# CtDSP_IO.net
KiCad netlist of a schematic drawn in Altium Designer
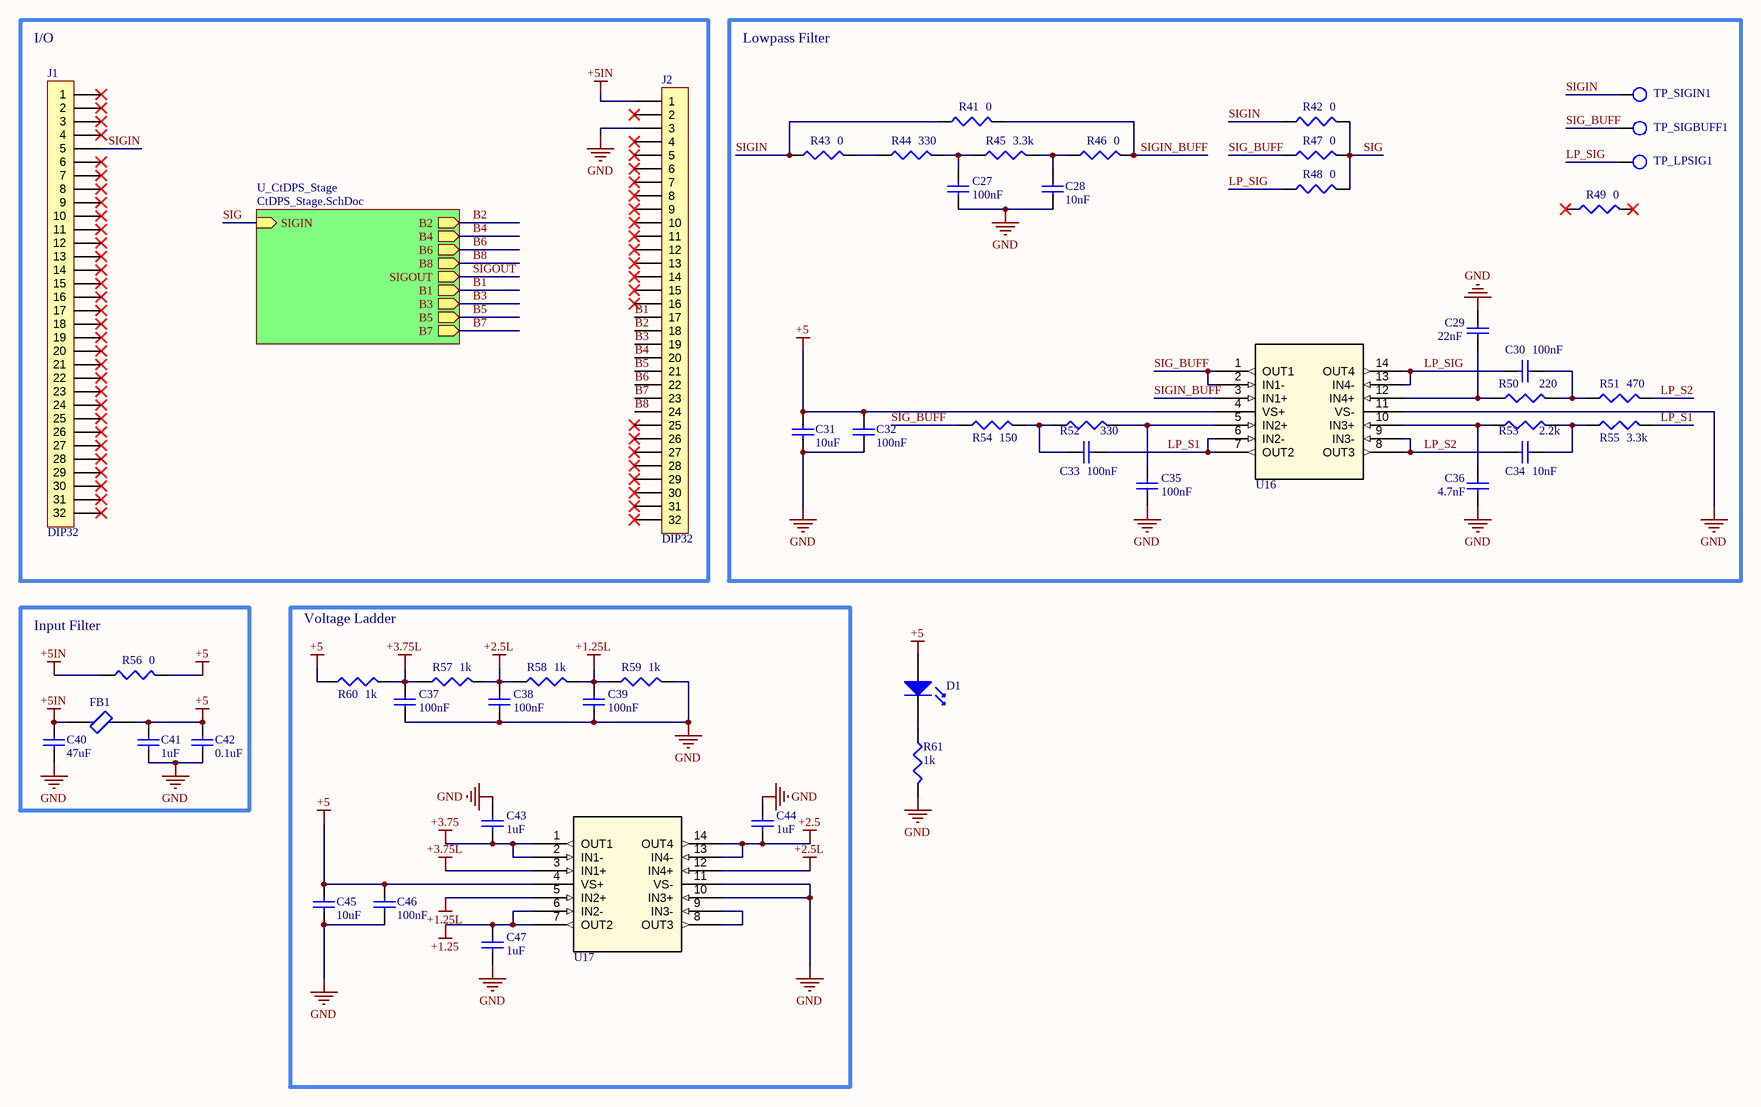
[diagram p0: CtDSP_IO.SchDoc]

(export (version "E")
  (design (tool "Eeschema 10.0.6"))
  (components
    (comp (ref "C27")
      (value "100nF")
      (footprint "C_0402")
      (fields (field (name "LCSC PART #") "C1525"))
      (libsource (lib "ctdsp") (part "C_0402"))
    )
    (comp (ref "C28")
      (value "10nF")
      (footprint "C_0402")
      (fields (field (name "LCSC PART #") "C15195"))
      (libsource (lib "ctdsp") (part "C_0402"))
    )
    (comp (ref "C29")
      (value "22nF")
      (footprint "C_0402")
      (fields (field (name "LCSC PART #") "C1532"))
      (libsource (lib "ctdsp") (part "C_0402"))
    )
    (comp (ref "C30")
      (value "100nF")
      (footprint "C_0402")
      (fields (field (name "LCSC PART #") "C1525"))
      (libsource (lib "ctdsp") (part "C_0402"))
    )
    (comp (ref "C31")
      (value "10uF")
      (footprint "C_0402")
      (fields (field (name "LCSC PART #") "C15525"))
      (libsource (lib "ctdsp") (part "C_0402"))
    )
    (comp (ref "C32")
      (value "100nF")
      (footprint "C_0402")
      (fields (field (name "LCSC PART #") "C1525"))
      (libsource (lib "ctdsp") (part "C_0402"))
    )
    (comp (ref "C33")
      (value "100nF")
      (footprint "C_0402")
      (fields (field (name "LCSC PART #") "C1525"))
      (libsource (lib "ctdsp") (part "C_0402"))
    )
    (comp (ref "C34")
      (value "10nF")
      (footprint "C_0402")
      (fields (field (name "LCSC PART #") "C15195"))
      (libsource (lib "ctdsp") (part "C_0402"))
    )
    (comp (ref "C35")
      (value "100nF")
      (footprint "C_0402")
      (fields (field (name "LCSC PART #") "C1525"))
      (libsource (lib "ctdsp") (part "C_0402"))
    )
    (comp (ref "C36")
      (value "4.7nF")
      (footprint "C_0402")
      (fields (field (name "LCSC PART #") "C1538"))
      (libsource (lib "ctdsp") (part "C_0402"))
    )
    (comp (ref "C37")
      (value "100nF")
      (footprint "C_0402")
      (fields (field (name "LCSC PART #") "C1525"))
      (libsource (lib "ctdsp") (part "C_0402"))
    )
    (comp (ref "C38")
      (value "100nF")
      (footprint "C_0402")
      (fields (field (name "LCSC PART #") "C1525"))
      (libsource (lib "ctdsp") (part "C_0402"))
    )
    (comp (ref "C39")
      (value "100nF")
      (footprint "C_0402")
      (fields (field (name "LCSC PART #") "C1525"))
      (libsource (lib "ctdsp") (part "C_0402"))
    )
    (comp (ref "C40")
      (value "47uF")
      (footprint "C_0805")
      (fields (field (name "LCSC PART #") "C16780"))
      (libsource (lib "ctdsp") (part "C_0805"))
    )
    (comp (ref "C41")
      (value "1uF")
      (footprint "C_0603")
      (fields (field (name "LCSC PART #") "C15849"))
      (libsource (lib "ctdsp") (part "C_0603"))
    )
    (comp (ref "C42")
      (value "0.1uF")
      (footprint "C_0402")
      (fields (field (name "LCSC PART #") "C1525"))
      (libsource (lib "ctdsp") (part "C_0402"))
    )
    (comp (ref "C43")
      (value "1uF")
      (footprint "C_0603")
      (fields (field (name "LCSC PART #") "C15849"))
      (libsource (lib "ctdsp") (part "C_0603"))
    )
    (comp (ref "C44")
      (value "1uF")
      (footprint "C_0603")
      (fields (field (name "LCSC PART #") "C15849"))
      (libsource (lib "ctdsp") (part "C_0603"))
    )
    (comp (ref "C45")
      (value "10uF")
      (footprint "C_0402")
      (fields (field (name "LCSC PART #") "C15525"))
      (libsource (lib "ctdsp") (part "C_0402"))
    )
    (comp (ref "C46")
      (value "100nF")
      (footprint "C_0402")
      (fields (field (name "LCSC PART #") "C1525"))
      (libsource (lib "ctdsp") (part "C_0402"))
    )
    (comp (ref "C47")
      (value "1uF")
      (footprint "C_0603")
      (fields (field (name "LCSC PART #") "C15849"))
      (libsource (lib "ctdsp") (part "C_0603"))
    )
    (comp (ref "D1")
      (value "LED_0603")
      (footprint "LED_6003")
      (fields (field (name "LCSC PART #") "C2286"))
      (libsource (lib "ctdsp") (part "LED_0603"))
    )
    (comp (ref "FB1")
      (value "BLM18PG121SN1D")
      (footprint "BLM18PG121SN1D")
      (description "-55℃~+125℃ 1 120Ω@100MHz 2A 50mΩ ±25% 0603 Ferrite Beads ROHS")
      (fields (field (name "LCSC PART #") "C14709"))
      (libsource (lib "ctdsp") (part "BLM18PG121SN1D"))
    )
    (comp (ref "J1") (value "DIP32") (footprint "DIP32") (libsource (lib "ctdsp") (part "DIP32")))
    (comp (ref "J2") (value "DIP32") (footprint "DIP32") (libsource (lib "") (part "DIP32_1")))
    (comp (ref "R41")
      (value "0")
      (footprint "RES_1206")
      (fields (field (name "LCSC PART #") "C17888"))
      (libsource (lib "ctdsp") (part "RES_1206"))
    )
    (comp (ref "R42")
      (value "0")
      (footprint "RES_1206")
      (fields (field (name "LCSC PART #") "C17888"))
      (libsource (lib "ctdsp") (part "RES_1206"))
    )
    (comp (ref "R43")
      (value "0")
      (footprint "RES_1206")
      (fields (field (name "LCSC PART #") "C17888"))
      (libsource (lib "ctdsp") (part "RES_1206"))
    )
    (comp (ref "R44")
      (value "330")
      (footprint "RES_0603")
      (fields (field (name "LCSC PART #") "C23138"))
      (libsource (lib "ctdsp") (part "RES_0603"))
    )
    (comp (ref "R45")
      (value "3.3k")
      (footprint "RES_0603")
      (fields (field (name "LCSC PART #") "C22978"))
      (libsource (lib "ctdsp") (part "RES_0603"))
    )
    (comp (ref "R46")
      (value "0")
      (footprint "RES_1206")
      (fields (field (name "LCSC PART #") "C17888"))
      (libsource (lib "ctdsp") (part "RES_1206"))
    )
    (comp (ref "R47")
      (value "0")
      (footprint "RES_1206")
      (fields (field (name "LCSC PART #") "C17888"))
      (libsource (lib "ctdsp") (part "RES_1206"))
    )
    (comp (ref "R48")
      (value "0")
      (footprint "RES_1206")
      (fields (field (name "LCSC PART #") "C17888"))
      (libsource (lib "ctdsp") (part "RES_1206"))
    )
    (comp (ref "R49")
      (value "0")
      (footprint "RES_1206")
      (fields (field (name "LCSC PART #") "C17888"))
      (libsource (lib "ctdsp") (part "RES_1206"))
    )
    (comp (ref "R50")
      (value "220")
      (footprint "RES_0402")
      (fields (field (name "LCSC PART #") "C25091"))
      (libsource (lib "ctdsp") (part "RES_0402"))
    )
    (comp (ref "R51")
      (value "470")
      (footprint "RES_0402")
      (fields (field (name "LCSC PART #") "C25117"))
      (libsource (lib "ctdsp") (part "RES_0402"))
    )
    (comp (ref "R52")
      (value "330")
      (footprint "RES_0603")
      (fields (field (name "LCSC PART #") "C23138"))
      (libsource (lib "ctdsp") (part "RES_0603"))
    )
    (comp (ref "R53")
      (value "2.2k")
      (footprint "RES_0603")
      (fields (field (name "LCSC PART #") "C4190"))
      (libsource (lib "ctdsp") (part "RES_0603"))
    )
    (comp (ref "R54")
      (value "150")
      (footprint "RES_0603")
      (fields (field (name "LCSC PART #") "C22808"))
      (libsource (lib "ctdsp") (part "RES_0603"))
    )
    (comp (ref "R55")
      (value "3.3k")
      (footprint "RES_0603")
      (fields (field (name "LCSC PART #") "C22978"))
      (libsource (lib "ctdsp") (part "RES_0603"))
    )
    (comp (ref "R56")
      (value "0")
      (footprint "RES_1206")
      (fields (field (name "LCSC PART #") "C17888"))
      (libsource (lib "ctdsp") (part "RES_1206"))
    )
    (comp (ref "R57")
      (value "1k")
      (footprint "RES_0603")
      (fields (field (name "LCSC PART #") "C5123612"))
      (libsource (lib "ctdsp") (part "RES_0603"))
    )
    (comp (ref "R58")
      (value "1k")
      (footprint "RES_0603")
      (fields (field (name "LCSC PART #") "C5123612"))
      (libsource (lib "ctdsp") (part "RES_0603"))
    )
    (comp (ref "R59")
      (value "1k")
      (footprint "RES_0603")
      (fields (field (name "LCSC PART #") "C5123612"))
      (libsource (lib "ctdsp") (part "RES_0603"))
    )
    (comp (ref "R60")
      (value "1k")
      (footprint "RES_0603")
      (fields (field (name "LCSC PART #") "C5123612"))
      (libsource (lib "ctdsp") (part "RES_0603"))
    )
    (comp (ref "R61")
      (value "1k")
      (footprint "RES_0402")
      (fields (field (name "LCSC PART #") "C11702"))
      (libsource (lib "ctdsp") (part "RES_0402"))
    )
    (comp (ref "TP_LPSIG1")
      (value "TESTPOINT")
      (footprint "TESTPOINT")
      (libsource (lib "ctdsp") (part "TESTPOINT"))
    )
    (comp (ref "TP_SIGBUFF1")
      (value "TESTPOINT")
      (footprint "TESTPOINT")
      (libsource (lib "ctdsp") (part "TESTPOINT"))
    )
    (comp (ref "TP_SIGIN1")
      (value "TESTPOINT")
      (footprint "TESTPOINT")
      (libsource (lib "ctdsp") (part "TESTPOINT"))
    )
    (comp (ref "U16")
      (value "ADA4891-4ARZ-R7")
      (footprint "ADA4891-4ARZ-R7")
      (description "Quad Rail-to-Rail Op-Amp, 240 MHz, 170 V/µs, SOT-23-5")
      (fields (field (name "LCSC PART #") "C654290"))
      (libsource (lib "ctdsp") (part "ADA4891-4ARZ-R7"))
    )
    (comp (ref "U17")
      (value "ADA4891-4ARZ-R7")
      (footprint "ADA4891-4ARZ-R7")
      (description "Quad Rail-to-Rail Op-Amp, 240 MHz, 170 V/µs, SOT-23-5")
      (fields (field (name "LCSC PART #") "C654290"))
      (libsource (lib "ctdsp") (part "ADA4891-4ARZ-R7"))
    )
  )
  (nets
    (net (code "1") (name "+1.25") (class "Default")
      (node (ref "C47") (pin "2") (pinfunction "2_2") (pintype "passive"))
      (node (ref "U17") (pin "6") (pinfunction "IN2-_6") (pintype "input"))
      (node (ref "U17") (pin "7") (pinfunction "OUT2_7") (pintype "output"))
    )
    (net (code "2") (name "+1.25L") (class "Default")
      (node (ref "C39") (pin "2") (pinfunction "2_2") (pintype "passive"))
      (node (ref "R58") (pin "2") (pinfunction "2_2") (pintype "passive"))
      (node (ref "R59") (pin "1") (pinfunction "1_1") (pintype "passive"))
      (node (ref "U17") (pin "5") (pinfunction "IN2+_5") (pintype "input"))
    )
    (net (code "3") (name "+2.5") (class "Default")
      (node (ref "C44") (pin "1") (pinfunction "1_1") (pintype "passive"))
      (node (ref "U17") (pin "13") (pinfunction "IN4-_13") (pintype "input"))
      (node (ref "U17") (pin "14") (pinfunction "OUT4_14") (pintype "output"))
    )
    (net (code "4") (name "+2.5L") (class "Default")
      (node (ref "C38") (pin "2") (pinfunction "2_2") (pintype "passive"))
      (node (ref "R57") (pin "2") (pinfunction "2_2") (pintype "passive"))
      (node (ref "R58") (pin "1") (pinfunction "1_1") (pintype "passive"))
      (node (ref "U17") (pin "12") (pinfunction "IN4+_12") (pintype "input"))
    )
    (net (code "5") (name "+3.75") (class "Default")
      (node (ref "C43") (pin "1") (pinfunction "1_1") (pintype "passive"))
      (node (ref "U17") (pin "1") (pinfunction "OUT1_1") (pintype "output"))
      (node (ref "U17") (pin "2") (pinfunction "IN1-_2") (pintype "input"))
    )
    (net (code "6") (name "+3.75L") (class "Default")
      (node (ref "C37") (pin "2") (pinfunction "2_2") (pintype "passive"))
      (node (ref "R57") (pin "1") (pinfunction "1_1") (pintype "passive"))
      (node (ref "R60") (pin "2") (pinfunction "2_2") (pintype "passive"))
      (node (ref "U17") (pin "3") (pinfunction "IN1+_3") (pintype "input"))
    )
    (net (code "7") (name "+5") (class "Default")
      (node (ref "C31") (pin "1") (pinfunction "1_1") (pintype "passive"))
      (node (ref "C32") (pin "2") (pinfunction "2_2") (pintype "passive"))
      (node (ref "C41") (pin "2") (pinfunction "2_2") (pintype "passive"))
      (node (ref "C42") (pin "1") (pinfunction "1_1") (pintype "passive"))
      (node (ref "C45") (pin "1") (pinfunction "1_1") (pintype "passive"))
      (node (ref "C46") (pin "2") (pinfunction "2_2") (pintype "passive"))
      (node (ref "D1") (pin "2") (pinfunction "K_2") (pintype "passive"))
      (node (ref "FB1") (pin "2") (pinfunction "2_2") (pintype "passive"))
      (node (ref "R56") (pin "2") (pinfunction "2_2") (pintype "passive"))
      (node (ref "R60") (pin "1") (pinfunction "1_1") (pintype "passive"))
      (node (ref "U16") (pin "4") (pinfunction "VS+_4") (pintype "power_in"))
      (node (ref "U17") (pin "4") (pinfunction "VS+_4") (pintype "power_in"))
    )
    (net (code "8") (name "+5IN") (class "Default")
      (node (ref "C40") (pin "2") (pinfunction "2_2") (pintype "passive"))
      (node (ref "FB1") (pin "1") (pinfunction "1_1") (pintype "passive"))
      (node (ref "J2") (pin "1") (pinfunction "1_1") (pintype "passive"))
      (node (ref "R56") (pin "1") (pinfunction "1_1") (pintype "passive"))
    )
    (net (code "9") (name "/B1") (class "Default")
      (node (ref "J2") (pin "17") (pinfunction "17_17") (pintype "passive"))
    )
    (net (code "10") (name "/B2") (class "Default")
      (node (ref "J2") (pin "18") (pinfunction "18_18") (pintype "passive"))
    )
    (net (code "11") (name "/B3") (class "Default")
      (node (ref "J2") (pin "19") (pinfunction "19_19") (pintype "passive"))
    )
    (net (code "12") (name "/B4") (class "Default")
      (node (ref "J2") (pin "20") (pinfunction "20_20") (pintype "passive"))
    )
    (net (code "13") (name "/B5") (class "Default")
      (node (ref "J2") (pin "21") (pinfunction "21_21") (pintype "passive"))
    )
    (net (code "14") (name "/B6") (class "Default")
      (node (ref "J2") (pin "22") (pinfunction "22_22") (pintype "passive"))
    )
    (net (code "15") (name "/B7") (class "Default")
      (node (ref "J2") (pin "23") (pinfunction "23_23") (pintype "passive"))
    )
    (net (code "16") (name "/B8") (class "Default")
      (node (ref "J2") (pin "24") (pinfunction "24_24") (pintype "passive"))
    )
    (net (code "17") (name "/LP_S1") (class "Default")
      (node (ref "C33") (pin "1") (pinfunction "1_1") (pintype "passive"))
      (node (ref "R55") (pin "2") (pinfunction "2_2") (pintype "passive"))
      (node (ref "U16") (pin "6") (pinfunction "IN2-_6") (pintype "input"))
      (node (ref "U16") (pin "7") (pinfunction "OUT2_7") (pintype "output"))
    )
    (net (code "18") (name "/LP_S2") (class "Default")
      (node (ref "C34") (pin "1") (pinfunction "1_1") (pintype "passive"))
      (node (ref "R51") (pin "2") (pinfunction "2_2") (pintype "passive"))
      (node (ref "U16") (pin "8") (pinfunction "OUT3_8") (pintype "output"))
      (node (ref "U16") (pin "9") (pinfunction "IN3-_9") (pintype "input"))
    )
    (net (code "19") (name "/LP_SIG") (class "Default")
      (node (ref "C30") (pin "2") (pinfunction "2_2") (pintype "passive"))
      (node (ref "R48") (pin "1") (pinfunction "1_1") (pintype "passive"))
      (node (ref "TP_LPSIG1") (pin "1") (pinfunction "1_1") (pintype "passive"))
      (node (ref "U16") (pin "13") (pinfunction "IN4-_13") (pintype "input"))
      (node (ref "U16") (pin "14") (pinfunction "OUT4_14") (pintype "output"))
    )
    (net (code "20") (name "/SIG") (class "Default")
      (node (ref "R42") (pin "2") (pinfunction "2_2") (pintype "passive"))
      (node (ref "R47") (pin "2") (pinfunction "2_2") (pintype "passive"))
      (node (ref "R48") (pin "2") (pinfunction "2_2") (pintype "passive"))
    )
    (net (code "21") (name "/SIGIN") (class "Default")
      (node (ref "J1") (pin "5") (pinfunction "5_5") (pintype "passive"))
      (node (ref "R41") (pin "1") (pinfunction "1_1") (pintype "passive"))
      (node (ref "R42") (pin "1") (pinfunction "1_1") (pintype "passive"))
      (node (ref "R43") (pin "1") (pinfunction "1_1") (pintype "passive"))
      (node (ref "TP_SIGIN1") (pin "1") (pinfunction "1_1") (pintype "passive"))
    )
    (net (code "22") (name "/SIGIN_BUFF") (class "Default")
      (node (ref "R41") (pin "2") (pinfunction "2_2") (pintype "passive"))
      (node (ref "R46") (pin "2") (pinfunction "2_2") (pintype "passive"))
      (node (ref "U16") (pin "3") (pinfunction "IN1+_3") (pintype "input"))
    )
    (net (code "24") (name "/SIG_BUFF") (class "Default")
      (node (ref "R47") (pin "1") (pinfunction "1_1") (pintype "passive"))
      (node (ref "R54") (pin "1") (pinfunction "1_1") (pintype "passive"))
      (node (ref "TP_SIGBUFF1") (pin "1") (pinfunction "1_1") (pintype "passive"))
      (node (ref "U16") (pin "1") (pinfunction "OUT1_1") (pintype "output"))
      (node (ref "U16") (pin "2") (pinfunction "IN1-_2") (pintype "input"))
    )
    (net (code "25") (name "GND") (class "Default")
      (node (ref "C27") (pin "1") (pinfunction "1_1") (pintype "passive"))
      (node (ref "C28") (pin "1") (pinfunction "1_1") (pintype "passive"))
      (node (ref "C29") (pin "2") (pinfunction "2_2") (pintype "passive"))
      (node (ref "C31") (pin "2") (pinfunction "2_2") (pintype "passive"))
      (node (ref "C32") (pin "1") (pinfunction "1_1") (pintype "passive"))
      (node (ref "C35") (pin "1") (pinfunction "1_1") (pintype "passive"))
      (node (ref "C36") (pin "1") (pinfunction "1_1") (pintype "passive"))
      (node (ref "C37") (pin "1") (pinfunction "1_1") (pintype "passive"))
      (node (ref "C38") (pin "1") (pinfunction "1_1") (pintype "passive"))
      (node (ref "C39") (pin "1") (pinfunction "1_1") (pintype "passive"))
      (node (ref "C40") (pin "1") (pinfunction "1_1") (pintype "passive"))
      (node (ref "C41") (pin "1") (pinfunction "1_1") (pintype "passive"))
      (node (ref "C42") (pin "2") (pinfunction "2_2") (pintype "passive"))
      (node (ref "C43") (pin "2") (pinfunction "2_2") (pintype "passive"))
      (node (ref "C44") (pin "2") (pinfunction "2_2") (pintype "passive"))
      (node (ref "C45") (pin "2") (pinfunction "2_2") (pintype "passive"))
      (node (ref "C46") (pin "1") (pinfunction "1_1") (pintype "passive"))
      (node (ref "C47") (pin "1") (pinfunction "1_1") (pintype "passive"))
      (node (ref "J2") (pin "3") (pinfunction "3_3") (pintype "passive"))
      (node (ref "R59") (pin "2") (pinfunction "2_2") (pintype "passive"))
      (node (ref "R61") (pin "2") (pinfunction "2_2") (pintype "passive"))
      (node (ref "U16") (pin "11") (pinfunction "VS-_11") (pintype "power_in"))
      (node (ref "U17") (pin "10") (pinfunction "IN3+_10") (pintype "input"))
      (node (ref "U17") (pin "11") (pinfunction "VS-_11") (pintype "power_in"))
    )
    (net (code "26") (name "Net-(C27-Pad2)") (class "Default")
      (node (ref "C27") (pin "2") (pinfunction "2_2") (pintype "passive"))
      (node (ref "R44") (pin "2") (pinfunction "2_2") (pintype "passive"))
      (node (ref "R45") (pin "1") (pinfunction "1_1") (pintype "passive"))
    )
    (net (code "27") (name "Net-(C28-Pad2)") (class "Default")
      (node (ref "C28") (pin "2") (pinfunction "2_2") (pintype "passive"))
      (node (ref "R45") (pin "2") (pinfunction "2_2") (pintype "passive"))
      (node (ref "R46") (pin "1") (pinfunction "1_1") (pintype "passive"))
    )
    (net (code "28") (name "Net-(C30-Pad1)") (class "Default")
      (node (ref "C30") (pin "1") (pinfunction "1_1") (pintype "passive"))
      (node (ref "R50") (pin "2") (pinfunction "2_2") (pintype "passive"))
      (node (ref "R51") (pin "1") (pinfunction "1_1") (pintype "passive"))
    )
    (net (code "29") (name "Net-(C33-Pad2)") (class "Default")
      (node (ref "C33") (pin "2") (pinfunction "2_2") (pintype "passive"))
      (node (ref "R52") (pin "1") (pinfunction "1_1") (pintype "passive"))
      (node (ref "R54") (pin "2") (pinfunction "2_2") (pintype "passive"))
    )
    (net (code "30") (name "Net-(C34-Pad2)") (class "Default")
      (node (ref "C34") (pin "2") (pinfunction "2_2") (pintype "passive"))
      (node (ref "R53") (pin "2") (pinfunction "2_2") (pintype "passive"))
      (node (ref "R55") (pin "1") (pinfunction "1_1") (pintype "passive"))
    )
    (net (code "31") (name "Net-(D1-A)") (class "Default")
      (node (ref "D1") (pin "1") (pinfunction "A_1") (pintype "passive"))
      (node (ref "R61") (pin "1") (pinfunction "1_1") (pintype "passive"))
    )
    (net (code "32") (name "Net-(R43-Pad2)") (class "Default")
      (node (ref "R43") (pin "2") (pinfunction "2_2") (pintype "passive"))
      (node (ref "R44") (pin "1") (pinfunction "1_1") (pintype "passive"))
    )
    (net (code "33") (name "Net-(U16-IN2+)") (class "Default")
      (node (ref "C35") (pin "2") (pinfunction "2_2") (pintype "passive"))
      (node (ref "R52") (pin "2") (pinfunction "2_2") (pintype "passive"))
      (node (ref "U16") (pin "5") (pinfunction "IN2+_5") (pintype "input"))
    )
    (net (code "34") (name "Net-(U16-IN3+)") (class "Default")
      (node (ref "C36") (pin "2") (pinfunction "2_2") (pintype "passive"))
      (node (ref "R53") (pin "1") (pinfunction "1_1") (pintype "passive"))
      (node (ref "U16") (pin "10") (pinfunction "IN3+_10") (pintype "input"))
    )
    (net (code "35") (name "Net-(U16-IN4+)") (class "Default")
      (node (ref "C29") (pin "1") (pinfunction "1_1") (pintype "passive"))
      (node (ref "R50") (pin "1") (pinfunction "1_1") (pintype "passive"))
      (node (ref "U16") (pin "12") (pinfunction "IN4+_12") (pintype "input"))
    )
    (net (code "36") (name "Net-(U17-IN3-)") (class "Default")
      (node (ref "U17") (pin "8") (pinfunction "OUT3_8") (pintype "output"))
      (node (ref "U17") (pin "9") (pinfunction "IN3-_9") (pintype "input"))
    )
    (net (code "37") (name "unconnected-(J1-Pad1)") (class "Default")
      (node (ref "J1") (pin "1") (pinfunction "1_1") (pintype "passive+no_connect"))
    )
    (net (code "38") (name "unconnected-(J1-Pad2)") (class "Default")
      (node (ref "J1") (pin "2") (pinfunction "2_2") (pintype "passive+no_connect"))
    )
    (net (code "39") (name "unconnected-(J1-Pad3)") (class "Default")
      (node (ref "J1") (pin "3") (pinfunction "3_3") (pintype "passive+no_connect"))
    )
    (net (code "40") (name "unconnected-(J1-Pad4)") (class "Default")
      (node (ref "J1") (pin "4") (pinfunction "4_4") (pintype "passive+no_connect"))
    )
    (net (code "41") (name "unconnected-(J1-Pad6)") (class "Default")
      (node (ref "J1") (pin "6") (pinfunction "6_6") (pintype "passive+no_connect"))
    )
    (net (code "42") (name "unconnected-(J1-Pad7)") (class "Default")
      (node (ref "J1") (pin "7") (pinfunction "7_7") (pintype "passive+no_connect"))
    )
    (net (code "43") (name "unconnected-(J1-Pad8)") (class "Default")
      (node (ref "J1") (pin "8") (pinfunction "8_8") (pintype "passive+no_connect"))
    )
    (net (code "44") (name "unconnected-(J1-Pad9)") (class "Default")
      (node (ref "J1") (pin "9") (pinfunction "9_9") (pintype "passive+no_connect"))
    )
    (net (code "45") (name "unconnected-(J1-Pad10)") (class "Default")
      (node (ref "J1") (pin "10") (pinfunction "10_10") (pintype "passive+no_connect"))
    )
    (net (code "46") (name "unconnected-(J1-Pad11)") (class "Default")
      (node (ref "J1") (pin "11") (pinfunction "11_11") (pintype "passive+no_connect"))
    )
    (net (code "47") (name "unconnected-(J1-Pad12)") (class "Default")
      (node (ref "J1") (pin "12") (pinfunction "12_12") (pintype "passive+no_connect"))
    )
    (net (code "48") (name "unconnected-(J1-Pad13)") (class "Default")
      (node (ref "J1") (pin "13") (pinfunction "13_13") (pintype "passive+no_connect"))
    )
    (net (code "49") (name "unconnected-(J1-Pad14)") (class "Default")
      (node (ref "J1") (pin "14") (pinfunction "14_14") (pintype "passive+no_connect"))
    )
    (net (code "50") (name "unconnected-(J1-Pad15)") (class "Default")
      (node (ref "J1") (pin "15") (pinfunction "15_15") (pintype "passive+no_connect"))
    )
    (net (code "51") (name "unconnected-(J1-Pad16)") (class "Default")
      (node (ref "J1") (pin "16") (pinfunction "16_16") (pintype "passive+no_connect"))
    )
    (net (code "52") (name "unconnected-(J1-Pad17)") (class "Default")
      (node (ref "J1") (pin "17") (pinfunction "17_17") (pintype "passive+no_connect"))
    )
    (net (code "53") (name "unconnected-(J1-Pad18)") (class "Default")
      (node (ref "J1") (pin "18") (pinfunction "18_18") (pintype "passive+no_connect"))
    )
    (net (code "54") (name "unconnected-(J1-Pad19)") (class "Default")
      (node (ref "J1") (pin "19") (pinfunction "19_19") (pintype "passive+no_connect"))
    )
    (net (code "55") (name "unconnected-(J1-Pad20)") (class "Default")
      (node (ref "J1") (pin "20") (pinfunction "20_20") (pintype "passive+no_connect"))
    )
    (net (code "56") (name "unconnected-(J1-Pad21)") (class "Default")
      (node (ref "J1") (pin "21") (pinfunction "21_21") (pintype "passive+no_connect"))
    )
    (net (code "57") (name "unconnected-(J1-Pad22)") (class "Default")
      (node (ref "J1") (pin "22") (pinfunction "22_22") (pintype "passive+no_connect"))
    )
    (net (code "58") (name "unconnected-(J1-Pad23)") (class "Default")
      (node (ref "J1") (pin "23") (pinfunction "23_23") (pintype "passive+no_connect"))
    )
    (net (code "59") (name "unconnected-(J1-Pad24)") (class "Default")
      (node (ref "J1") (pin "24") (pinfunction "24_24") (pintype "passive+no_connect"))
    )
    (net (code "60") (name "unconnected-(J1-Pad25)") (class "Default")
      (node (ref "J1") (pin "25") (pinfunction "25_25") (pintype "passive+no_connect"))
    )
    (net (code "61") (name "unconnected-(J1-Pad26)") (class "Default")
      (node (ref "J1") (pin "26") (pinfunction "26_26") (pintype "passive+no_connect"))
    )
    (net (code "62") (name "unconnected-(J1-Pad27)") (class "Default")
      (node (ref "J1") (pin "27") (pinfunction "27_27") (pintype "passive+no_connect"))
    )
    (net (code "63") (name "unconnected-(J1-Pad28)") (class "Default")
      (node (ref "J1") (pin "28") (pinfunction "28_28") (pintype "passive+no_connect"))
    )
    (net (code "64") (name "unconnected-(J1-Pad29)") (class "Default")
      (node (ref "J1") (pin "29") (pinfunction "29_29") (pintype "passive+no_connect"))
    )
    (net (code "65") (name "unconnected-(J1-Pad30)") (class "Default")
      (node (ref "J1") (pin "30") (pinfunction "30_30") (pintype "passive+no_connect"))
    )
    (net (code "66") (name "unconnected-(J1-Pad31)") (class "Default")
      (node (ref "J1") (pin "31") (pinfunction "31_31") (pintype "passive+no_connect"))
    )
    (net (code "67") (name "unconnected-(J1-Pad32)") (class "Default")
      (node (ref "J1") (pin "32") (pinfunction "32_32") (pintype "passive+no_connect"))
    )
    (net (code "68") (name "unconnected-(J2-Pad2)") (class "Default")
      (node (ref "J2") (pin "2") (pinfunction "2_2") (pintype "passive+no_connect"))
    )
    (net (code "69") (name "unconnected-(J2-Pad4)") (class "Default")
      (node (ref "J2") (pin "4") (pinfunction "4_4") (pintype "passive+no_connect"))
    )
    (net (code "70") (name "unconnected-(J2-Pad5)") (class "Default")
      (node (ref "J2") (pin "5") (pinfunction "5_5") (pintype "passive+no_connect"))
    )
    (net (code "71") (name "unconnected-(J2-Pad6)") (class "Default")
      (node (ref "J2") (pin "6") (pinfunction "6_6") (pintype "passive+no_connect"))
    )
    (net (code "72") (name "unconnected-(J2-Pad7)") (class "Default")
      (node (ref "J2") (pin "7") (pinfunction "7_7") (pintype "passive+no_connect"))
    )
    (net (code "73") (name "unconnected-(J2-Pad8)") (class "Default")
      (node (ref "J2") (pin "8") (pinfunction "8_8") (pintype "passive+no_connect"))
    )
    (net (code "74") (name "unconnected-(J2-Pad9)") (class "Default")
      (node (ref "J2") (pin "9") (pinfunction "9_9") (pintype "passive+no_connect"))
    )
    (net (code "75") (name "unconnected-(J2-Pad10)") (class "Default")
      (node (ref "J2") (pin "10") (pinfunction "10_10") (pintype "passive+no_connect"))
    )
    (net (code "76") (name "unconnected-(J2-Pad11)") (class "Default")
      (node (ref "J2") (pin "11") (pinfunction "11_11") (pintype "passive+no_connect"))
    )
    (net (code "77") (name "unconnected-(J2-Pad12)") (class "Default")
      (node (ref "J2") (pin "12") (pinfunction "12_12") (pintype "passive+no_connect"))
    )
    (net (code "78") (name "unconnected-(J2-Pad13)") (class "Default")
      (node (ref "J2") (pin "13") (pinfunction "13_13") (pintype "passive+no_connect"))
    )
    (net (code "79") (name "unconnected-(J2-Pad14)") (class "Default")
      (node (ref "J2") (pin "14") (pinfunction "14_14") (pintype "passive+no_connect"))
    )
    (net (code "80") (name "unconnected-(J2-Pad15)") (class "Default")
      (node (ref "J2") (pin "15") (pinfunction "15_15") (pintype "passive+no_connect"))
    )
    (net (code "81") (name "unconnected-(J2-Pad16)") (class "Default")
      (node (ref "J2") (pin "16") (pinfunction "16_16") (pintype "passive+no_connect"))
    )
    (net (code "82") (name "unconnected-(J2-Pad25)") (class "Default")
      (node (ref "J2") (pin "25") (pinfunction "25_25") (pintype "passive+no_connect"))
    )
    (net (code "83") (name "unconnected-(J2-Pad26)") (class "Default")
      (node (ref "J2") (pin "26") (pinfunction "26_26") (pintype "passive+no_connect"))
    )
    (net (code "84") (name "unconnected-(J2-Pad27)") (class "Default")
      (node (ref "J2") (pin "27") (pinfunction "27_27") (pintype "passive+no_connect"))
    )
    (net (code "85") (name "unconnected-(J2-Pad28)") (class "Default")
      (node (ref "J2") (pin "28") (pinfunction "28_28") (pintype "passive+no_connect"))
    )
    (net (code "86") (name "unconnected-(J2-Pad29)") (class "Default")
      (node (ref "J2") (pin "29") (pinfunction "29_29") (pintype "passive+no_connect"))
    )
    (net (code "87") (name "unconnected-(J2-Pad30)") (class "Default")
      (node (ref "J2") (pin "30") (pinfunction "30_30") (pintype "passive+no_connect"))
    )
    (net (code "88") (name "unconnected-(J2-Pad31)") (class "Default")
      (node (ref "J2") (pin "31") (pinfunction "31_31") (pintype "passive+no_connect"))
    )
    (net (code "89") (name "unconnected-(J2-Pad32)") (class "Default")
      (node (ref "J2") (pin "32") (pinfunction "32_32") (pintype "passive+no_connect"))
    )
    (net (code "90") (name "unconnected-(R49-Pad1)") (class "Default")
      (node (ref "R49") (pin "1") (pinfunction "1_1") (pintype "passive+no_connect"))
    )
    (net (code "91") (name "unconnected-(R49-Pad2)") (class "Default")
      (node (ref "R49") (pin "2") (pinfunction "2_2") (pintype "passive+no_connect"))
    )
  )
)
